# untitled.net
KiCad netlist of a schematic drawn in EAGLE
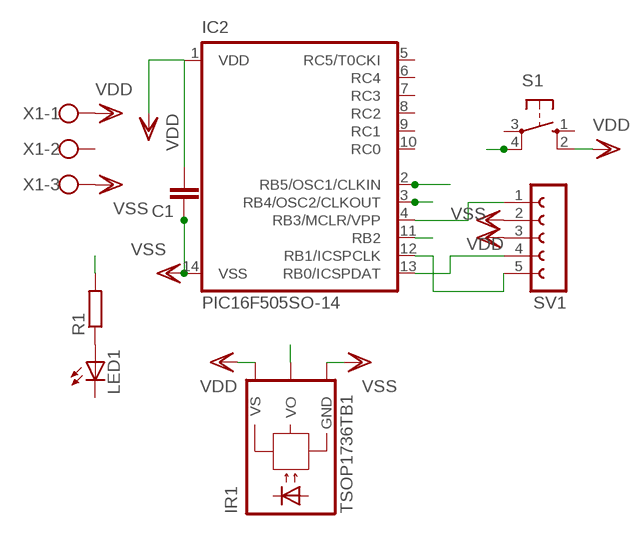
[diagram p0: schematic, sheet 1]

(export (version "E")
  (design (tool "Eeschema 10.0.6"))
  (components
    (comp (ref "C1")
      (value "C-EUC0805")
      (footprint "eagle-import:C0805")
      (libsource (lib "eagle-import") (part "C-EUC0805"))
    )
    (comp (ref "IC2")
      (value "PIC16F505SO-14")
      (footprint "eagle-import:SO-14")
      (libsource (lib "eagle-import") (part "PIC16F505SO-14"))
    )
    (comp (ref "IR1")
      (value "TSOP1736TB1")
      (footprint "eagle-import:TSOP17_TB1")
      (libsource (lib "eagle-import") (part "TSOP17TB136"))
    )
    (comp (ref "LED1")
      (value "LEDCHIP-LED0603")
      (footprint "eagle-import:CHIP-LED0603")
      (libsource (lib "eagle-import") (part "LEDCHIP-LED0603"))
    )
    (comp (ref "R1")
      (value "R-EU_R0805")
      (footprint "eagle-import:R0805")
      (libsource (lib "eagle-import") (part "R-EU_R0805"))
    )
    (comp (ref "S1")
      (value "10-XX")
      (footprint "eagle-import:B3F-10XX")
      (fields (field (name "MPN") "B3F-1000"))
      (libsource (lib "eagle-import") (part "10-XX"))
    )
    (comp (ref "SV1")
      (value "FE05-1")
      (footprint "eagle-import:FE05-1")
      (libsource (lib "eagle-import") (part "FE05-1"))
    )
    (comp (ref "X1")
      (value "W237-103")
      (footprint "eagle-import:W237-103")
      (fields (field (name "MPN") "237-103"))
      (libsource (lib "eagle-import") (part "W237-103"))
    )
  )
  (nets
    (net (code "1") (name "/RB2") (class "Default")
      (node (ref "IC2") (pin "11") (pinfunction "RB2_11") (pintype "bidirectional"))
      (node (ref "S1") (pin "4") (pinfunction "P1_4") (pintype "passive"))
    )
    (net (code "2") (name "/RB4") (class "Default")
      (node (ref "IC2") (pin "3") (pinfunction "RB4/OSC2/CLKOUT_3") (pintype "bidirectional"))
      (node (ref "R1") (pin "2") (pinfunction "2_2") (pintype "passive"))
    )
    (net (code "3") (name "/RB5") (class "Default")
      (node (ref "IC2") (pin "2") (pinfunction "RB5/OSC1/CLKIN_2") (pintype "bidirectional"))
      (node (ref "IR1") (pin "VO") (pinfunction "VO_VO") (pintype "open_collector"))
    )
    (net (code "4") (name "Net-(IC2-RB0{slash}ICSPDAT)") (class "Default")
      (node (ref "IC2") (pin "13") (pinfunction "RB0/ICSPDAT_13") (pintype "bidirectional"))
      (node (ref "SV1") (pin "4") (pinfunction "4_4") (pintype "passive"))
    )
    (net (code "5") (name "Net-(IC2-RB1{slash}ICSPCLK)") (class "Default")
      (node (ref "IC2") (pin "12") (pinfunction "RB1/ICSPCLK_12") (pintype "bidirectional"))
      (node (ref "SV1") (pin "5") (pinfunction "5_5") (pintype "passive"))
    )
    (net (code "6") (name "Net-(IC2-RB3{slash}MCLR{slash}VPP)") (class "Default")
      (node (ref "IC2") (pin "4") (pinfunction "RB3/MCLR/VPP_4") (pintype "bidirectional"))
      (node (ref "SV1") (pin "1") (pinfunction "1_1") (pintype "passive"))
    )
    (net (code "7") (name "Net-(LED1-PadA)") (class "Default")
      (node (ref "LED1") (pin "A") (pinfunction "A_A") (pintype "passive"))
      (node (ref "R1") (pin "1") (pinfunction "1_1") (pintype "passive"))
    )
    (net (code "8") (name "VDD") (class "Default")
      (node (ref "C1") (pin "2") (pinfunction "2_2") (pintype "passive"))
      (node (ref "IC2") (pin "1") (pinfunction "VDD_1") (pintype "power_in"))
      (node (ref "IR1") (pin "VS") (pinfunction "VS_VS") (pintype "power_in"))
      (node (ref "S1") (pin "2") (pinfunction "S1_2") (pintype "passive"))
      (node (ref "SV1") (pin "2") (pinfunction "2_2") (pintype "passive"))
      (node (ref "X1") (pin "1") (pinfunction "KL_1") (pintype "passive"))
    )
    (net (code "9") (name "VSS") (class "Default")
      (node (ref "C1") (pin "1") (pinfunction "1_1") (pintype "passive"))
      (node (ref "IC2") (pin "14") (pinfunction "VSS_14") (pintype "power_in"))
      (node (ref "IR1") (pin "GND") (pinfunction "GND_GND") (pintype "power_in"))
      (node (ref "SV1") (pin "3") (pinfunction "3_3") (pintype "passive"))
      (node (ref "X1") (pin "3") (pinfunction "KL_3") (pintype "passive"))
    )
    (net (code "10") (name "unconnected-(IC2-RC0-Pad10)") (class "Default")
      (node (ref "IC2") (pin "10") (pinfunction "RC0_10") (pintype "bidirectional"))
    )
    (net (code "11") (name "unconnected-(IC2-RC1-Pad9)") (class "Default")
      (node (ref "IC2") (pin "9") (pinfunction "RC1_9") (pintype "bidirectional"))
    )
    (net (code "12") (name "unconnected-(IC2-RC2-Pad8)") (class "Default")
      (node (ref "IC2") (pin "8") (pinfunction "RC2_8") (pintype "bidirectional"))
    )
    (net (code "13") (name "unconnected-(IC2-RC3-Pad7)") (class "Default")
      (node (ref "IC2") (pin "7") (pinfunction "RC3_7") (pintype "bidirectional"))
    )
    (net (code "14") (name "unconnected-(IC2-RC4-Pad6)") (class "Default")
      (node (ref "IC2") (pin "6") (pinfunction "RC4_6") (pintype "bidirectional"))
    )
    (net (code "15") (name "unconnected-(IC2-RC5{slash}T0CKI-Pad5)") (class "Default")
      (node (ref "IC2") (pin "5") (pinfunction "RC5/T0CKI_5") (pintype "bidirectional"))
    )
    (net (code "16") (name "unconnected-(LED1-PadC)") (class "Default")
      (node (ref "LED1") (pin "C") (pinfunction "C_C") (pintype "passive"))
    )
    (net (code "17") (name "unconnected-(S1-P-Pad3)") (class "Default")
      (node (ref "S1") (pin "3") (pinfunction "P_3") (pintype "passive"))
    )
    (net (code "18") (name "unconnected-(S1-S-Pad1)") (class "Default")
      (node (ref "S1") (pin "1") (pinfunction "S_1") (pintype "passive"))
    )
    (net (code "19") (name "unconnected-(X1B-KL-Pad2)") (class "Default")
      (node (ref "X1") (pin "2") (pinfunction "KL_2") (pintype "passive"))
    )
  )
)
